# MB1297_USB_OTG_FS.net
KiCad netlist of a schematic drawn in Altium Designer
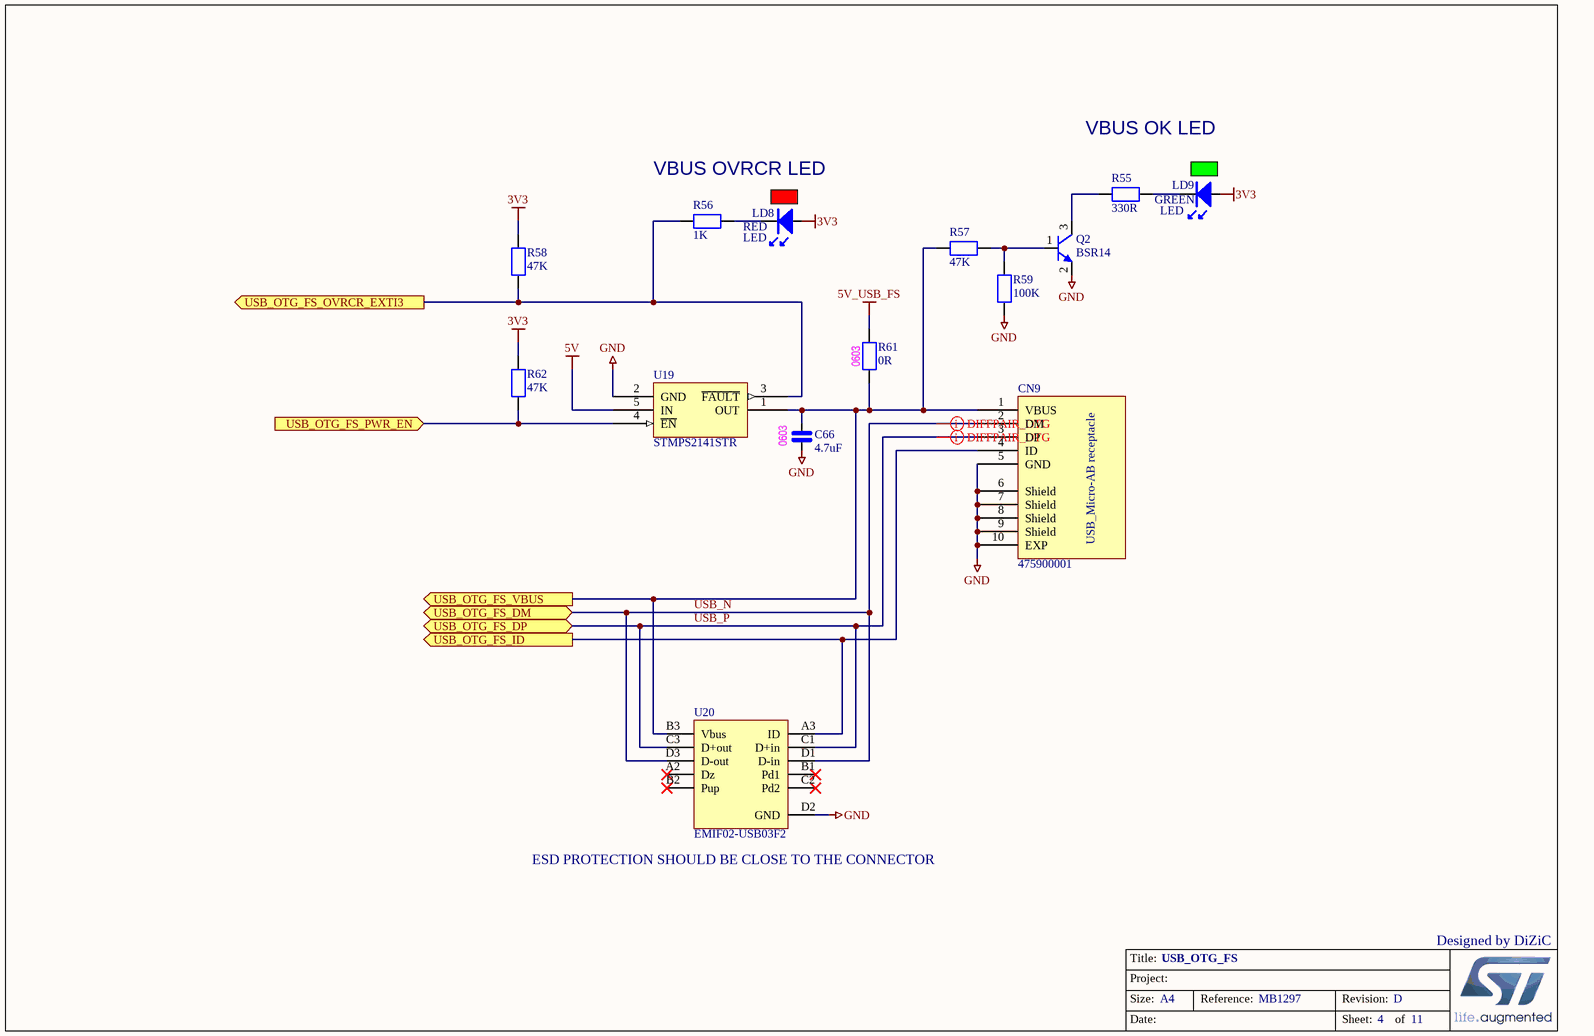
[diagram p0: MB1297_USB_OTG_FS.SchDoc]

(export (version "E")
  (design (tool "Eeschema 10.0.6"))
  (components
    (comp (ref "C66")
      (value "4.7uF")
      (footprint "0603_CAP_NPOL")
      (description "Capacitor_not polarized")
      (libsource (lib "ST_Lib3D") (part "CAP_NPOL"))
    )
    (comp (ref "CN9")
      (value "475900001")
      (footprint "CON_USBMICROAB_MOLEX_47590-0001_H3")
      (description "USB-MICRO-AB, 47590-0001, SMT, MOLEX")
      (libsource (lib "MCD_TEMP_PCH") (part "475900001"))
    )
    (comp (ref "LD8")
      (value "LED")
      (footprint "0603_LED_RED")
      (description "Light-Emitting Diode")
      (fields (field (name "COLOR") "RED"))
      (libsource (lib "ST_Lib3D") (part "LED"))
    )
    (comp (ref "LD9")
      (value "LED")
      (footprint "0603_LED_GREEN")
      (description "Light-Emitting Diode")
      (fields (field (name "COLOR") "GREEN"))
      (libsource (lib "ST_Lib3D") (part "LED"))
    )
    (comp (ref "Q2")
      (value "BSR14")
      (footprint "ST_Lib3D:SOT23-3")
      (description "BSR14 NPN switching transistor SOT23 (Marking U8)")
      (libsource (lib "ST_Lib3D") (part "BSR14"))
    )
    (comp (ref "R55")
      (value "330R")
      (footprint "0402_RES")
      (description "Resistor")
      (libsource (lib "Lib3D_Altium10_Schlib") (part "RES"))
    )
    (comp (ref "R56")
      (value "1K")
      (footprint "0402_RES")
      (description "Resistor")
      (libsource (lib "Lib3D_Altium10_Schlib") (part "RES"))
    )
    (comp (ref "R57")
      (value "47K")
      (footprint "0402_RES")
      (description "Resistor")
      (libsource (lib "Lib3D_Altium10_Schlib") (part "RES"))
    )
    (comp (ref "R58")
      (value "47K")
      (footprint "0402_RES")
      (description "Resistor")
      (libsource (lib "Lib3D_Altium10_Schlib") (part "RES"))
    )
    (comp (ref "R59")
      (value "100K")
      (footprint "0402_RES")
      (description "Resistor")
      (libsource (lib "Lib3D_Altium10_Schlib") (part "RES"))
    )
    (comp (ref "R61")
      (value "0R")
      (footprint "0603_RES")
      (description "Resistor")
      (libsource (lib "Lib3D_Altium10_Schlib") (part "RES"))
    )
    (comp (ref "R62")
      (value "47K")
      (footprint "0402_RES")
      (description "Resistor")
      (libsource (lib "Lib3D_Altium10_Schlib") (part "RES"))
    )
    (comp (ref "U19")
      (value "STMPS2141STR")
      (footprint "MOS_SOT23-5L")
      (description "Enhanced single channel power switches")
      (libsource (lib "MCD_TEMP_PCH") (part "STMPS2141STR"))
    )
    (comp (ref "U20")
      (value "EMIF02-USB03F2")
      (footprint "ESD_FLIP-CHIP-BGA11_1P44X1P94_P050")
      (description "2-line IPAD, EMI filter including ESD protection")
      (libsource (lib "MCD_TEMP_PCH") (part "EMIF02-USB03F2"))
    )
  )
  (nets
    (net (code "1") (name "/USB_N") (class "Default")
      (node (ref "CN9") (pin "2") (pinfunction "DM_2") (pintype "passive"))
      (node (ref "U20") (pin "D1") (pinfunction "D-in_D1") (pintype "passive"))
      (node (ref "U20") (pin "D3") (pinfunction "D-out_D3") (pintype "passive"))
    )
    (net (code "2") (name "/USB_OTG_FS_ID") (class "Default")
      (node (ref "CN9") (pin "4") (pinfunction "ID_4") (pintype "passive"))
      (node (ref "U20") (pin "A3") (pinfunction "ID_A3") (pintype "passive"))
    )
    (net (code "3") (name "/USB_OTG_FS_OVRCR_EXTI3") (class "Default")
      (node (ref "R56") (pin "1") (pinfunction "1_1") (pintype "passive"))
      (node (ref "R58") (pin "2") (pinfunction "2_2") (pintype "passive"))
      (node (ref "U19") (pin "3") (pinfunction "~{FAULT}_3") (pintype "output"))
    )
    (net (code "4") (name "/USB_OTG_FS_PWR_EN") (class "Default")
      (node (ref "R62") (pin "2") (pinfunction "2_2") (pintype "passive"))
      (node (ref "U19") (pin "4") (pinfunction "~{EN}_4") (pintype "input"))
    )
    (net (code "5") (name "/USB_OTG_FS_VBUS") (class "Default")
      (node (ref "C66") (pin "1") (pinfunction "1_1") (pintype "passive"))
      (node (ref "CN9") (pin "1") (pinfunction "VBUS_1") (pintype "passive"))
      (node (ref "R57") (pin "1") (pinfunction "1_1") (pintype "passive"))
      (node (ref "R61") (pin "2") (pinfunction "2_2") (pintype "passive"))
      (node (ref "U19") (pin "1") (pinfunction "OUT_1") (pintype "passive"))
      (node (ref "U20") (pin "B3") (pinfunction "Vbus_B3") (pintype "passive"))
    )
    (net (code "6") (name "/USB_P") (class "Default")
      (node (ref "CN9") (pin "3") (pinfunction "DP_3") (pintype "passive"))
      (node (ref "U20") (pin "C1") (pinfunction "D+in_C1") (pintype "passive"))
      (node (ref "U20") (pin "C3") (pinfunction "D+out_C3") (pintype "passive"))
    )
    (net (code "7") (name "3V3") (class "Default")
      (node (ref "LD8") (pin "A") (pinfunction "A_A") (pintype "passive"))
      (node (ref "LD9") (pin "A") (pinfunction "A_A") (pintype "passive"))
      (node (ref "R58") (pin "1") (pinfunction "1_1") (pintype "passive"))
      (node (ref "R62") (pin "1") (pinfunction "1_1") (pintype "passive"))
    )
    (net (code "8") (name "5V") (class "Default")
      (node (ref "U19") (pin "5") (pinfunction "IN_5") (pintype "passive"))
    )
    (net (code "9") (name "5V_USB_FS") (class "Default")
      (node (ref "R61") (pin "1") (pinfunction "1_1") (pintype "passive"))
    )
    (net (code "10") (name "GND") (class "Default")
      (node (ref "C66") (pin "2") (pinfunction "2_2") (pintype "passive"))
      (node (ref "CN9") (pin "10") (pinfunction "EXP_10") (pintype "passive"))
      (node (ref "CN9") (pin "5") (pinfunction "GND_5") (pintype "passive"))
      (node (ref "CN9") (pin "6") (pinfunction "Shield_6") (pintype "passive"))
      (node (ref "CN9") (pin "7") (pinfunction "Shield_7") (pintype "passive"))
      (node (ref "CN9") (pin "8") (pinfunction "Shield_8") (pintype "passive"))
      (node (ref "CN9") (pin "9") (pinfunction "Shield_9") (pintype "passive"))
      (node (ref "Q2") (pin "2") (pinfunction "E_2") (pintype "passive"))
      (node (ref "R59") (pin "1") (pinfunction "1_1") (pintype "passive"))
      (node (ref "U19") (pin "2") (pinfunction "GND_2") (pintype "passive"))
      (node (ref "U20") (pin "D2") (pinfunction "GND_D2") (pintype "passive"))
    )
    (net (code "11") (name "Net-(LD8-PadK)") (class "Default")
      (node (ref "LD8") (pin "K") (pinfunction "K_K") (pintype "passive"))
      (node (ref "R56") (pin "2") (pinfunction "2_2") (pintype "passive"))
    )
    (net (code "12") (name "Net-(LD9-PadK)") (class "Default")
      (node (ref "LD9") (pin "K") (pinfunction "K_K") (pintype "passive"))
      (node (ref "R55") (pin "2") (pinfunction "2_2") (pintype "passive"))
    )
    (net (code "13") (name "Net-(Q2-B)") (class "Default")
      (node (ref "Q2") (pin "1") (pinfunction "B_1") (pintype "passive"))
      (node (ref "R57") (pin "2") (pinfunction "2_2") (pintype "passive"))
      (node (ref "R59") (pin "2") (pinfunction "2_2") (pintype "passive"))
    )
    (net (code "14") (name "Net-(Q2-C)") (class "Default")
      (node (ref "Q2") (pin "3") (pinfunction "C_3") (pintype "passive"))
      (node (ref "R55") (pin "1") (pinfunction "1_1") (pintype "passive"))
    )
    (net (code "15") (name "unconnected-(U20-Dz-PadA2)") (class "Default")
      (node (ref "U20") (pin "A2") (pinfunction "Dz_A2") (pintype "passive+no_connect"))
    )
    (net (code "16") (name "unconnected-(U20-Pd1-PadB1)") (class "Default")
      (node (ref "U20") (pin "B1") (pinfunction "Pd1_B1") (pintype "passive+no_connect"))
    )
    (net (code "17") (name "unconnected-(U20-Pd2-PadC2)") (class "Default")
      (node (ref "U20") (pin "C2") (pinfunction "Pd2_C2") (pintype "passive+no_connect"))
    )
    (net (code "18") (name "unconnected-(U20-Pup-PadB2)") (class "Default")
      (node (ref "U20") (pin "B2") (pinfunction "Pup_B2") (pintype "passive+no_connect"))
    )
  )
)
